# Smartcar.net
KiCad netlist of a schematic drawn in Altium Designer
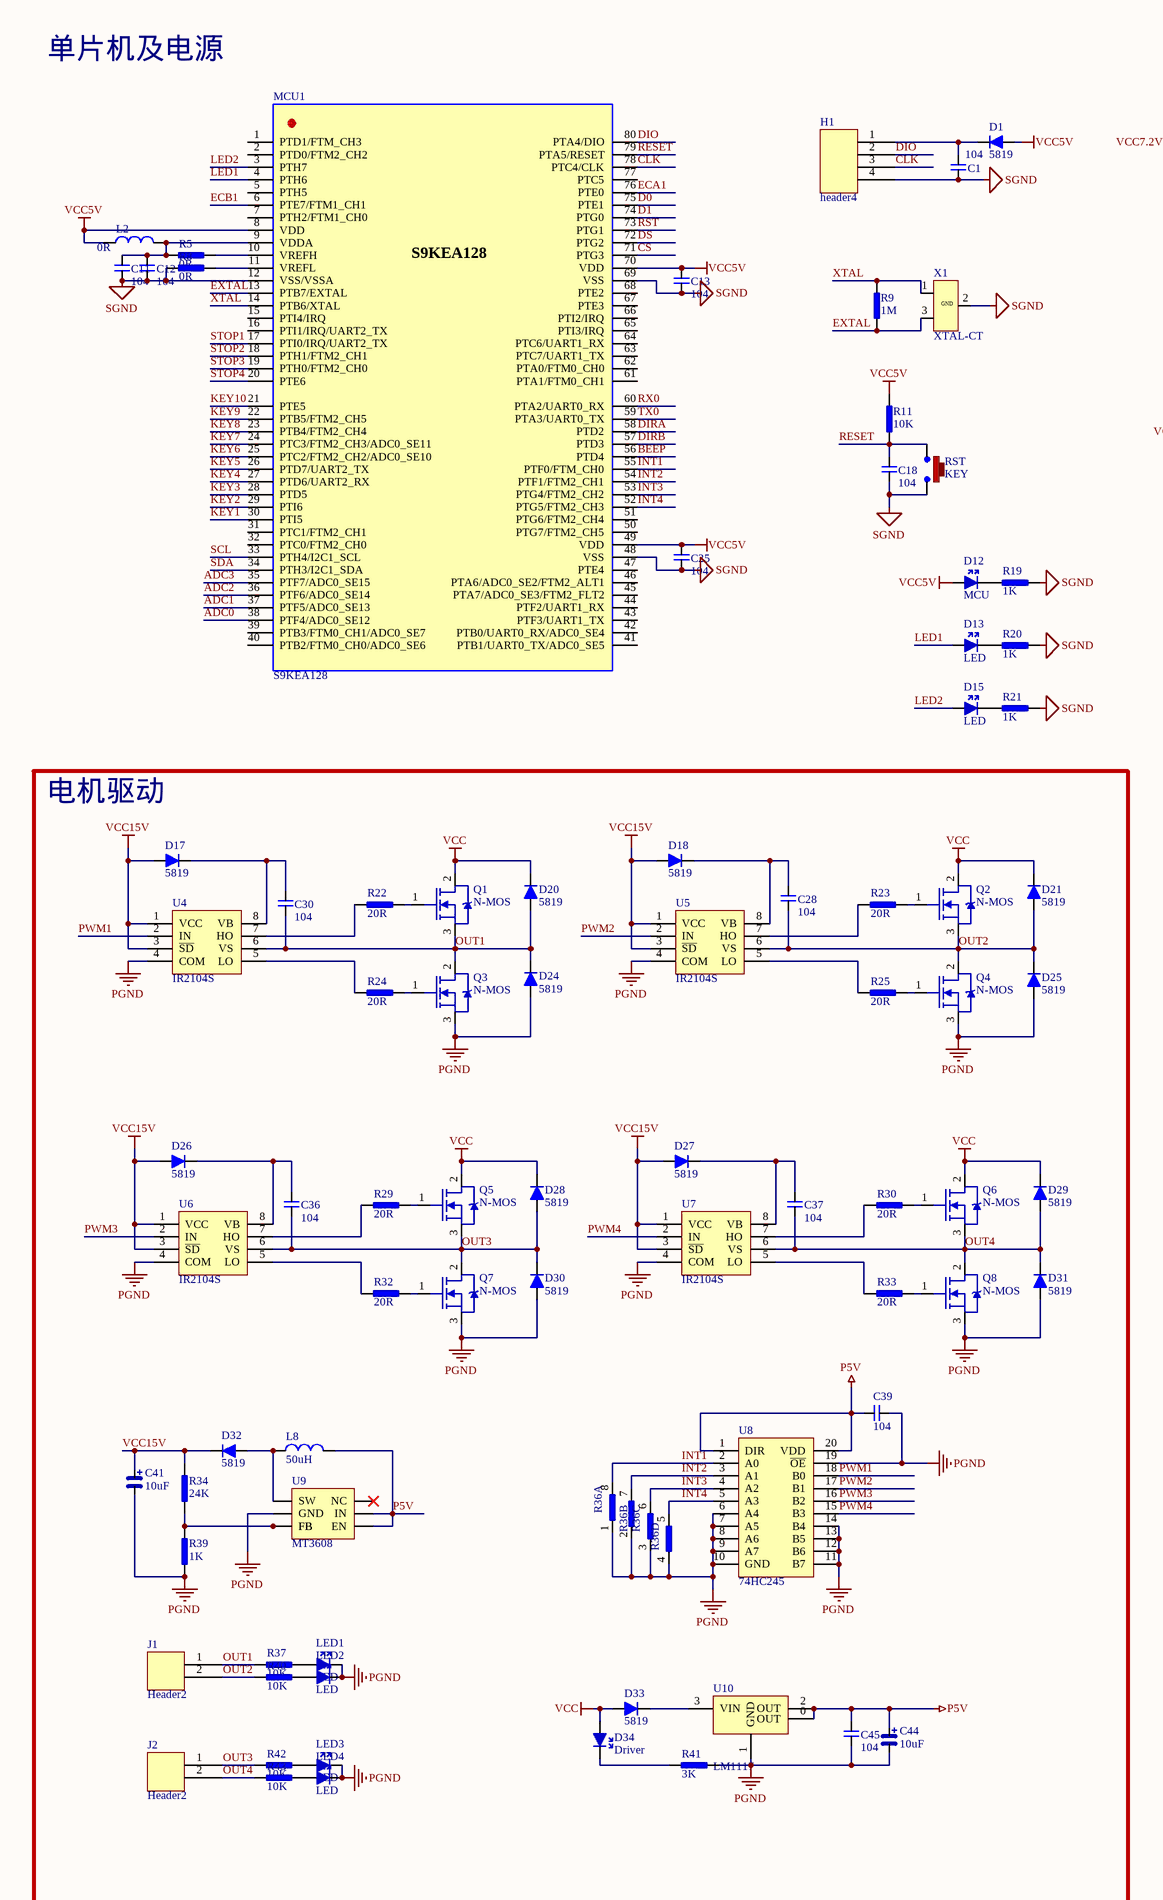
[diagram p0: Smartcar.SchDoc, left]
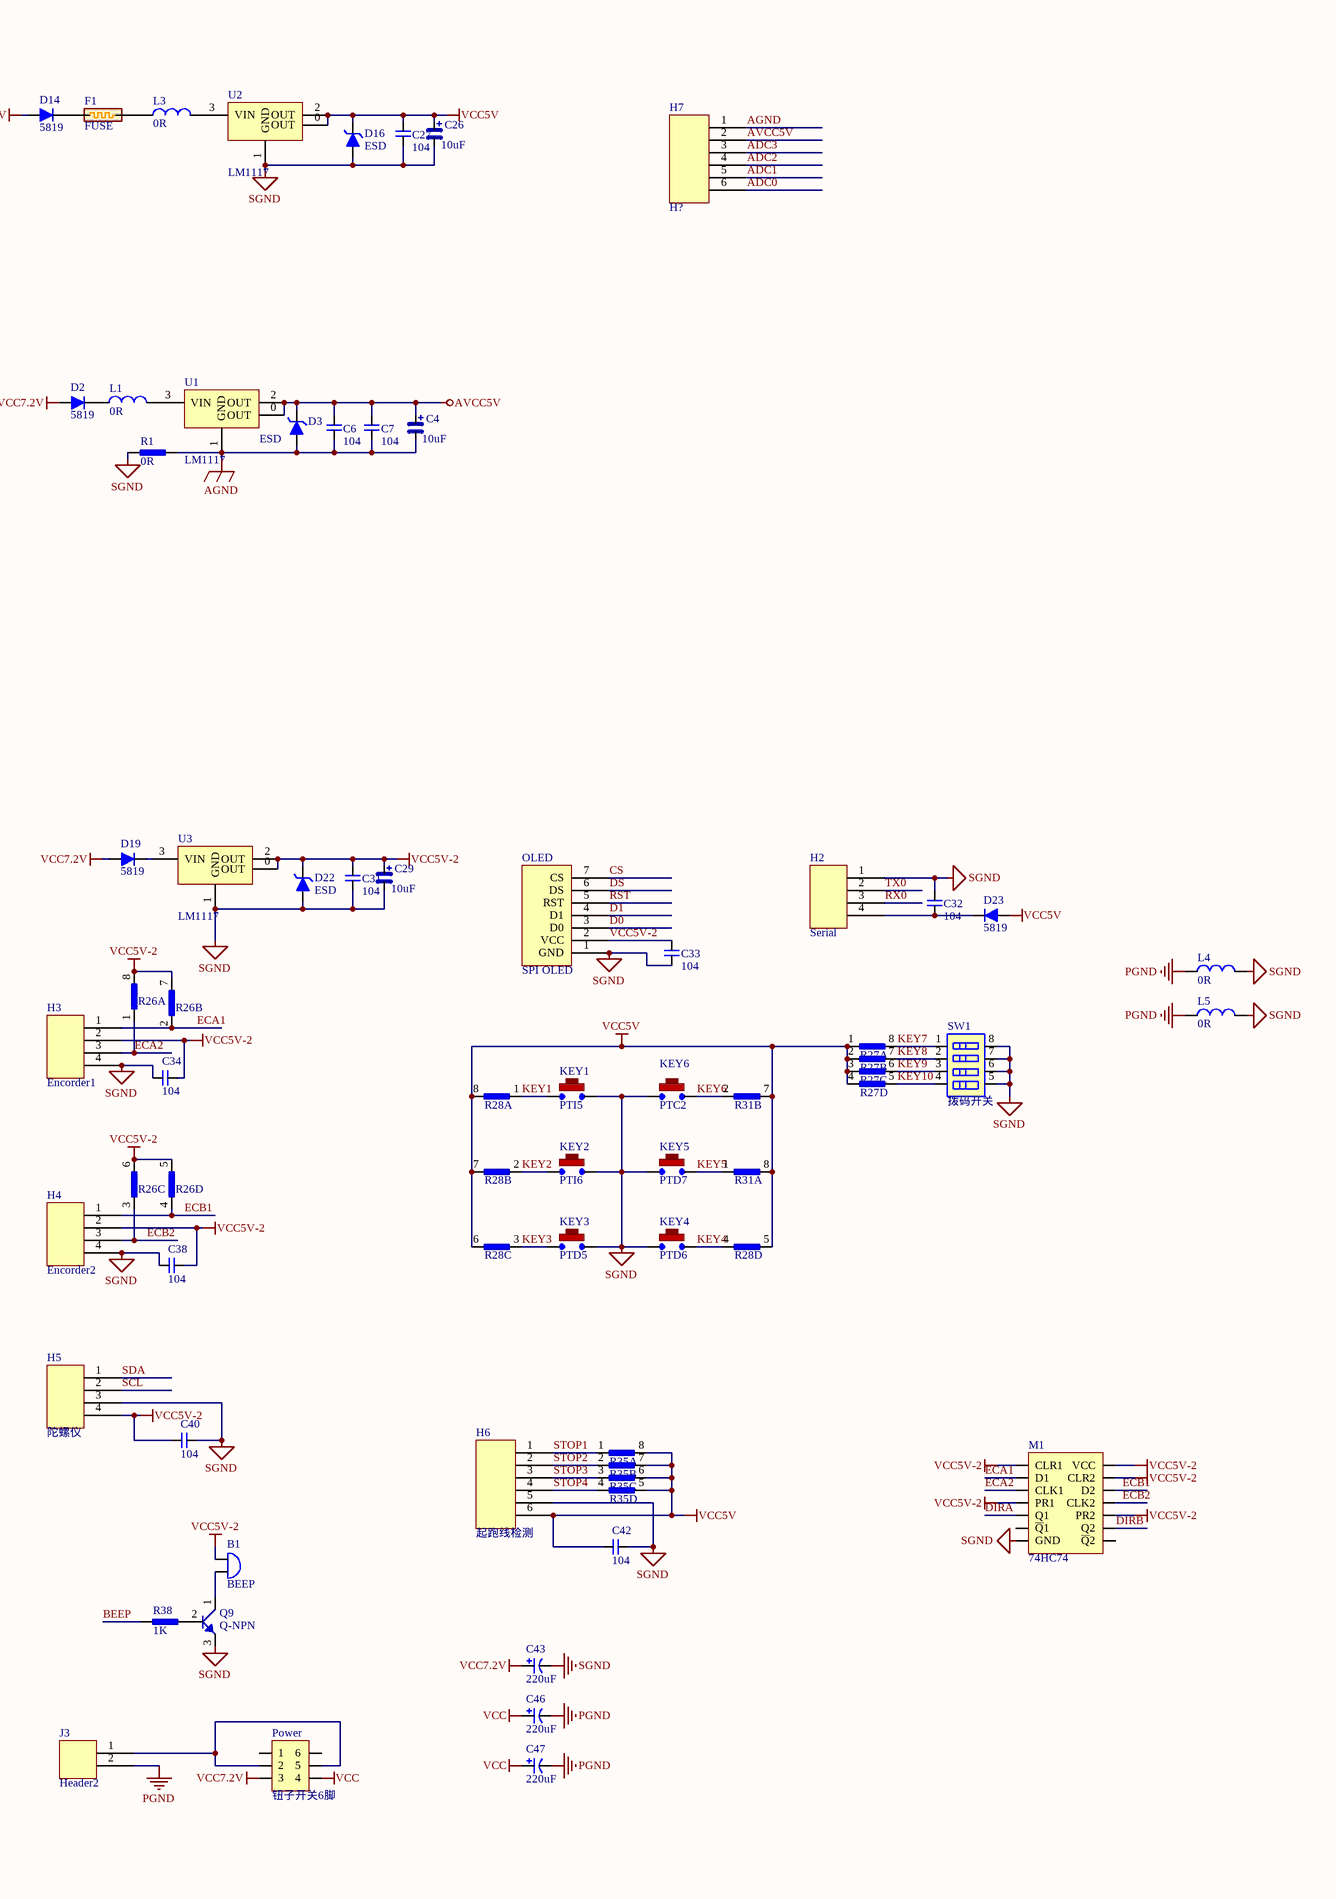
[diagram p1: Smartcar.SchDoc, right]

(export (version "E")
  (design (tool "Eeschema 10.0.6"))
  (components
    (comp (ref "B1") (value "BEEP") (footprint "BEEP") (libsource (lib "常用原理图库") (part "BEEP")))
    (comp (ref "C1") (value "104") (footprint "C0603") (libsource (lib "常用原理图库") (part "CAP")))
    (comp (ref "C4") (value "10uF") (footprint "TAN 3215") (libsource (lib "常用原理图库") (part "C-TAN")))
    (comp (ref "C6") (value "104") (footprint "C0603") (libsource (lib "常用原理图库") (part "CAP")))
    (comp (ref "C7") (value "104") (footprint "C0603") (libsource (lib "常用原理图库") (part "CAP")))
    (comp (ref "C11") (value "104") (footprint "C0603") (libsource (lib "常用原理图库") (part "CAP")))
    (comp (ref "C12") (value "104") (footprint "C0603") (libsource (lib "常用原理图库") (part "CAP")))
    (comp (ref "C13") (value "104") (footprint "C0603") (libsource (lib "常用原理图库") (part "CAP")))
    (comp (ref "C18") (value "104") (footprint "C0603") (libsource (lib "常用原理图库") (part "CAP")))
    (comp (ref "C25") (value "104") (footprint "C0603") (libsource (lib "常用原理图库") (part "CAP")))
    (comp (ref "C26") (value "10uF") (footprint "TAN 3215") (libsource (lib "常用原理图库") (part "C-TAN")))
    (comp (ref "C27") (value "104") (footprint "C0603") (libsource (lib "常用原理图库") (part "CAP")))
    (comp (ref "C28") (value "104") (footprint "C0603") (libsource (lib "常用原理图库") (part "CAP")))
    (comp (ref "C29") (value "10uF") (footprint "TAN 3215") (libsource (lib "常用原理图库") (part "C-TAN")))
    (comp (ref "C30") (value "104") (footprint "C0603") (libsource (lib "常用原理图库") (part "CAP")))
    (comp (ref "C31") (value "104") (footprint "C0603") (libsource (lib "常用原理图库") (part "CAP")))
    (comp (ref "C32") (value "104") (footprint "C0603") (libsource (lib "常用原理图库") (part "CAP")))
    (comp (ref "C33") (value "104") (footprint "C0603") (libsource (lib "常用原理图库") (part "CAP")))
    (comp (ref "C34") (value "104") (footprint "C0603") (libsource (lib "常用原理图库") (part "CAP")))
    (comp (ref "C36") (value "104") (footprint "C0603") (libsource (lib "常用原理图库") (part "CAP")))
    (comp (ref "C37") (value "104") (footprint "C0603") (libsource (lib "常用原理图库") (part "CAP")))
    (comp (ref "C38") (value "104") (footprint "C0603") (libsource (lib "常用原理图库") (part "CAP")))
    (comp (ref "C39") (value "104") (footprint "C0603") (libsource (lib "常用原理图库") (part "CAP")))
    (comp (ref "C40") (value "104") (footprint "C0603") (libsource (lib "常用原理图库") (part "CAP")))
    (comp (ref "C41") (value "10uF") (footprint "TAN 3215") (libsource (lib "常用原理图库") (part "C-TAN")))
    (comp (ref "C42") (value "104") (footprint "C0603") (libsource (lib "常用原理图库") (part "CAP")))
    (comp (ref "C43") (value "220uF") (footprint "CAP6.6X6.6") (libsource (lib "常用原理图库") (part "CAP-SMD")))
    (comp (ref "C44") (value "10uF") (footprint "TAN 3215") (libsource (lib "常用原理图库") (part "C-TAN")))
    (comp (ref "C45") (value "104") (footprint "C0603") (libsource (lib "常用原理图库") (part "CAP")))
    (comp (ref "C46") (value "220uF") (footprint "CAP6.6X6.6") (libsource (lib "常用原理图库") (part "CAP-SMD")))
    (comp (ref "C47") (value "220uF") (footprint "CAP6.6X6.6") (libsource (lib "常用原理图库") (part "CAP-SMD")))
    (comp (ref "D1") (value "5819") (footprint "SOD323") (libsource (lib "常用原理图库") (part "diode")))
    (comp (ref "D2") (value "5819") (footprint "SOD323") (libsource (lib "常用原理图库") (part "diode")))
    (comp (ref "D3") (value "ESD") (footprint "SOD323") (libsource (lib "常用原理图库") (part "D-ESD")))
    (comp (ref "D12") (value "MCU") (footprint "0603LED") (libsource (lib "常用原理图库") (part "LED")))
    (comp (ref "D13") (value "LED") (footprint "0603LED") (libsource (lib "常用原理图库") (part "LED")))
    (comp (ref "D14") (value "5819") (footprint "SOD123") (libsource (lib "常用原理图库") (part "diode")))
    (comp (ref "D15") (value "LED") (footprint "0603LED") (libsource (lib "常用原理图库") (part "LED")))
    (comp (ref "D16") (value "ESD") (footprint "SOD323") (libsource (lib "常用原理图库") (part "D-ESD")))
    (comp (ref "D17") (value "5819") (footprint "SOD123") (libsource (lib "常用原理图库") (part "Diode")))
    (comp (ref "D18") (value "5819") (footprint "SOD123") (libsource (lib "常用原理图库") (part "Diode")))
    (comp (ref "D19") (value "5819") (footprint "SOD323") (libsource (lib "常用原理图库") (part "diode")))
    (comp (ref "D20") (value "5819") (footprint "SOD323") (libsource (lib "常用原理图库") (part "Diode")))
    (comp (ref "D21") (value "5819") (footprint "SOD323") (libsource (lib "常用原理图库") (part "Diode")))
    (comp (ref "D22") (value "ESD") (footprint "SOD323") (libsource (lib "常用原理图库") (part "D-ESD")))
    (comp (ref "D23") (value "5819") (footprint "SOD323") (libsource (lib "常用原理图库") (part "Diode")))
    (comp (ref "D24") (value "5819") (footprint "SOD323") (libsource (lib "常用原理图库") (part "Diode")))
    (comp (ref "D25") (value "5819") (footprint "SOD323") (libsource (lib "常用原理图库") (part "Diode")))
    (comp (ref "D26") (value "5819") (footprint "SOD123") (libsource (lib "常用原理图库") (part "Diode")))
    (comp (ref "D27") (value "5819") (footprint "SOD123") (libsource (lib "常用原理图库") (part "Diode")))
    (comp (ref "D28") (value "5819") (footprint "SOD323") (libsource (lib "常用原理图库") (part "Diode")))
    (comp (ref "D29") (value "5819") (footprint "SOD323") (libsource (lib "常用原理图库") (part "Diode")))
    (comp (ref "D30") (value "5819") (footprint "SOD323") (libsource (lib "常用原理图库") (part "Diode")))
    (comp (ref "D31") (value "5819") (footprint "SOD323") (libsource (lib "常用原理图库") (part "Diode")))
    (comp (ref "D32") (value "5819") (footprint "SOD123") (libsource (lib "常用原理图库") (part "Diode")))
    (comp (ref "D33") (value "5819") (footprint "SOD123") (libsource (lib "常用原理图库") (part "diode")))
    (comp (ref "D34") (value "Driver") (footprint "0603LED") (libsource (lib "常用原理图库") (part "LED")))
    (comp (ref "F1") (value "FUSE") (footprint "R 0805") (libsource (lib "常用原理图库") (part "FUSE")))
    (comp (ref "H1") (value "header4") (footprint "HDR1X4") (libsource (lib "常用原理图库") (part "header4")))
    (comp (ref "H2") (value "Serial") (footprint "HDR1X4") (libsource (lib "常用原理图库") (part "header4")))
    (comp (ref "H3")
      (value "Encorder1")
      (footprint "1.25mm卧贴-4P")
      (libsource (lib "常用原理图库") (part "header4"))
    )
    (comp (ref "H4")
      (value "Encorder2")
      (footprint "1.25mm卧贴-4P")
      (libsource (lib "常用原理图库") (part "header4"))
    )
    (comp (ref "H5") (value "陀螺仪") (footprint "1.25mm卧贴-4P") (libsource (lib "常用原理图库") (part "header4")))
    (comp (ref "H6") (value "起跑线检测") (footprint "1.25mm卧贴-6P") (libsource (lib "常用原理图库") (part "header6")))
    (comp (ref "H7") (value "H?") (footprint "1.25mm卧贴-6P") (libsource (lib "常用原理图库") (part "header6")))
    (comp (ref "J1") (value "Header2") (footprint "motor") (libsource (lib "常用原理图库") (part "Header2")))
    (comp (ref "J2") (value "Header2") (footprint "MOTOR-R") (libsource (lib "常用原理图库") (part "Header2")))
    (comp (ref "J3") (value "Header2") (footprint "POWER-IN") (libsource (lib "常用原理图库") (part "Header2")))
    (comp (ref "KEY1") (value "PTI5") (footprint "轻触开关贴片") (libsource (lib "常用原理图库") (part "KEY")))
    (comp (ref "KEY2") (value "PTI6") (footprint "轻触开关贴片") (libsource (lib "常用原理图库") (part "KEY")))
    (comp (ref "KEY3") (value "PTD5") (footprint "轻触开关贴片") (libsource (lib "常用原理图库") (part "KEY")))
    (comp (ref "KEY4") (value "PTD6") (footprint "轻触开关贴片") (libsource (lib "常用原理图库") (part "KEY")))
    (comp (ref "KEY5") (value "PTD7") (footprint "轻触开关贴片") (libsource (lib "常用原理图库") (part "KEY")))
    (comp (ref "KEY6") (value "PTC2") (footprint "轻触开关贴片") (libsource (lib "常用原理图库") (part "KEY")))
    (comp (ref "L1") (value "0R") (footprint "L0603") (libsource (lib "常用原理图库") (part "Inductance")))
    (comp (ref "L2") (value "0R") (footprint "L0603") (libsource (lib "常用原理图库") (part "Inductance")))
    (comp (ref "L3") (value "0R") (footprint "L0603") (libsource (lib "常用原理图库") (part "Inductance")))
    (comp (ref "L4") (value "0R") (footprint "L0603") (libsource (lib "常用原理图库") (part "Inductance")))
    (comp (ref "L5") (value "0R") (footprint "L0603") (libsource (lib "常用原理图库") (part "Inductance")))
    (comp (ref "L8") (value "50uH") (footprint "L-06030") (libsource (lib "常用原理图库") (part "Inductance")))
    (comp (ref "LED1") (value "LED") (footprint "0603LED") (libsource (lib "常用原理图库") (part "LED")))
    (comp (ref "LED2") (value "LED") (footprint "0603LED") (libsource (lib "常用原理图库") (part "LED")))
    (comp (ref "LED3") (value "LED") (footprint "0603LED") (libsource (lib "常用原理图库") (part "LED")))
    (comp (ref "LED4") (value "LED") (footprint "0603LED") (libsource (lib "常用原理图库") (part "LED")))
    (comp (ref "M1") (value "74HC74") (footprint "ssoic14") (libsource (lib "常用原理图库") (part "74HC74")))
    (comp (ref "MCU1") (value "S9KEA128") (footprint "LQFP80") (libsource (lib "Smartcar") (part "S9KEA128")))
    (comp (ref "OLED")
      (value "SPI OLED")
      (footprint "OLED12864")
      (libsource (lib "常用原理图库") (part "SPI OLED"))
    )
    (comp (ref "Power") (value "钮子开关6脚") (footprint "钮子开关6脚") (libsource (lib "常用原理图库") (part "钮子开关6脚")))
    (comp (ref "Q1") (value "N-MOS") (footprint "常用封装:TO-252") (libsource (lib "常用原理图库") (part "N-MOS")))
    (comp (ref "Q2") (value "N-MOS") (footprint "常用封装:TO-252") (libsource (lib "常用原理图库") (part "N-MOS")))
    (comp (ref "Q3") (value "N-MOS") (footprint "常用封装:TO-252") (libsource (lib "常用原理图库") (part "N-MOS")))
    (comp (ref "Q4") (value "N-MOS") (footprint "常用封装:TO-252") (libsource (lib "常用原理图库") (part "N-MOS")))
    (comp (ref "Q5") (value "N-MOS") (footprint "常用封装:TO-252") (libsource (lib "常用原理图库") (part "N-MOS")))
    (comp (ref "Q6") (value "N-MOS") (footprint "常用封装:TO-252") (libsource (lib "常用原理图库") (part "N-MOS")))
    (comp (ref "Q7") (value "N-MOS") (footprint "常用封装:TO-252") (libsource (lib "常用原理图库") (part "N-MOS")))
    (comp (ref "Q8") (value "N-MOS") (footprint "常用封装:TO-252") (libsource (lib "常用原理图库") (part "N-MOS")))
    (comp (ref "Q9") (value "Q-NPN") (footprint "SOT-23") (libsource (lib "常用原理图库") (part "Q-NPN")))
    (comp (ref "R1") (value "0R") (footprint "R0603") (libsource (lib "常用原理图库") (part "RES")))
    (comp (ref "R5") (value "0R") (footprint "R0603") (libsource (lib "常用原理图库") (part "RES")))
    (comp (ref "R8") (value "0R") (footprint "R0603") (libsource (lib "常用原理图库") (part "RES")))
    (comp (ref "R9") (value "1M") (footprint "R0603") (libsource (lib "") (part "RES_1")))
    (comp (ref "R11") (value "10K") (footprint "R0603") (libsource (lib "") (part "RES_2")))
    (comp (ref "R19") (value "1K") (footprint "R0603") (libsource (lib "常用原理图库") (part "RES")))
    (comp (ref "R20") (value "1K") (footprint "R0603") (libsource (lib "常用原理图库") (part "RES")))
    (comp (ref "R21") (value "1K") (footprint "R0603") (libsource (lib "常用原理图库") (part "RES")))
    (comp (ref "R22") (value "20R") (footprint "R0603") (libsource (lib "常用原理图库") (part "RES")))
    (comp (ref "R23") (value "20R") (footprint "R0603") (libsource (lib "常用原理图库") (part "RES")))
    (comp (ref "R24") (value "20R") (footprint "R0603") (libsource (lib "常用原理图库") (part "RES")))
    (comp (ref "R25") (value "20R") (footprint "R0603") (libsource (lib "常用原理图库") (part "RES")))
    (comp (ref "R26")
      (value "Res Pack-4R")
      (footprint "8P4R-0603")
      (description "排阻")
      (fields (field (name "PUBLISHER") "Altium Limited"))
      (libsource (lib "") (part "Res Pack-4R_1"))
    )
    (comp (ref "R27")
      (value "Res Pack-4R")
      (footprint "8P4R-0603")
      (description "排阻")
      (fields (field (name "PUBLISHER") "Altium Limited"))
      (libsource (lib "常用原理图库") (part "Res Pack-4R"))
    )
    (comp (ref "R28")
      (value "Res Pack-4R")
      (footprint "8P4R-0603")
      (description "排阻")
      (fields (field (name "PUBLISHER") "Altium Limited"))
      (libsource (lib "常用原理图库") (part "Res Pack-4R"))
    )
    (comp (ref "R29") (value "20R") (footprint "R0603") (libsource (lib "常用原理图库") (part "RES")))
    (comp (ref "R30") (value "20R") (footprint "R0603") (libsource (lib "常用原理图库") (part "RES")))
    (comp (ref "R31")
      (value "Res Pack-4R")
      (footprint "8P4R-0603")
      (description "排阻")
      (fields (field (name "PUBLISHER") "Altium Limited"))
      (libsource (lib "常用原理图库") (part "Res Pack-4R"))
    )
    (comp (ref "R32") (value "20R") (footprint "R0603") (libsource (lib "常用原理图库") (part "RES")))
    (comp (ref "R33") (value "20R") (footprint "R0603") (libsource (lib "常用原理图库") (part "RES")))
    (comp (ref "R34") (value "24K") (footprint "R0603") (libsource (lib "") (part "RES_1")))
    (comp (ref "R35")
      (value "10K")
      (footprint "8P4R-0603")
      (description "排阻")
      (fields (field (name "PUBLISHER") "Altium Limited"))
      (libsource (lib "常用原理图库") (part "Res Pack-4R"))
    )
    (comp (ref "R36")
      (value "Res Pack-4R")
      (footprint "8P4R-0603")
      (description "排阻")
      (fields (field (name "PUBLISHER") "Altium Limited"))
      (libsource (lib "") (part "Res Pack-4R_1"))
    )
    (comp (ref "R37") (value "10K") (footprint "R0603") (libsource (lib "常用原理图库") (part "RES")))
    (comp (ref "R38") (value "1K") (footprint "R0603") (libsource (lib "常用原理图库") (part "RES")))
    (comp (ref "R39") (value "1K") (footprint "R0603") (libsource (lib "") (part "RES_1")))
    (comp (ref "R40") (value "10K") (footprint "R0603") (libsource (lib "常用原理图库") (part "RES")))
    (comp (ref "R41") (value "3K") (footprint "R0603") (libsource (lib "常用原理图库") (part "RES")))
    (comp (ref "R42") (value "10K") (footprint "R0603") (libsource (lib "常用原理图库") (part "RES")))
    (comp (ref "R43") (value "10K") (footprint "R0603") (libsource (lib "常用原理图库") (part "RES")))
    (comp (ref "RST") (value "KEY") (footprint "轻触开关贴片") (libsource (lib "") (part "KEY_1")))
    (comp (ref "SW1")
      (value "拨码开关")
      (footprint "SW-DIP-4 - duplicate")
      (libsource (lib "Smartcar") (part "拨码开关"))
    )
    (comp (ref "U1") (value "LM1117") (footprint "SOT223") (libsource (lib "") (part "1117_1")))
    (comp (ref "U2") (value "LM1117") (footprint "SOT223") (libsource (lib "常用原理图库") (part "1117")))
    (comp (ref "U3") (value "LM1117") (footprint "SOT223") (libsource (lib "常用原理图库") (part "1117")))
    (comp (ref "U4")
      (value "IR2104S")
      (footprint "SOP-8")
      (description "半桥驱动器")
      (libsource (lib "MOS电机驱动") (part "IR2104S"))
    )
    (comp (ref "U5")
      (value "IR2104S")
      (footprint "SOP-8")
      (description "半桥驱动器")
      (libsource (lib "MOS电机驱动") (part "IR2104S"))
    )
    (comp (ref "U6")
      (value "IR2104S")
      (footprint "SOP-8")
      (description "半桥驱动器")
      (libsource (lib "MOS电机驱动") (part "IR2104S"))
    )
    (comp (ref "U7")
      (value "IR2104S")
      (footprint "SOP-8")
      (description "半桥驱动器")
      (libsource (lib "MOS电机驱动") (part "IR2104S"))
    )
    (comp (ref "U8") (value "74HC245") (footprint "TSSOP-20") (libsource (lib "常用原理图库") (part "74HC245")))
    (comp (ref "U9") (value "MT3608") (footprint "SOT23-6") (libsource (lib "常用原理图库") (part "MT3608")))
    (comp (ref "U10") (value "LM1117") (footprint "SOT223") (libsource (lib "常用原理图库") (part "1117")))
    (comp (ref "X1") (value "XTAL-CT") (footprint "CSTCE8M") (libsource (lib "常用原理图库") (part "XTAL-CT")))
  )
  (nets
    (net (code "1") (name "/ADC0") (class "Default")
      (node (ref "H7") (pin "6") (pintype "passive"))
      (node (ref "MCU1") (pin "38") (pinfunction "PTF4/ADC0_SE12_38") (pintype "passive"))
    )
    (net (code "2") (name "/ADC1") (class "Default")
      (node (ref "H7") (pin "5") (pintype "passive"))
      (node (ref "MCU1") (pin "37") (pinfunction "PTF5/ADC0_SE13_37") (pintype "passive"))
    )
    (net (code "3") (name "/ADC2") (class "Default")
      (node (ref "H7") (pin "4") (pintype "passive"))
      (node (ref "MCU1") (pin "36") (pinfunction "PTF6/ADC0_SE14_36") (pintype "passive"))
    )
    (net (code "4") (name "/ADC3") (class "Default")
      (node (ref "H7") (pin "3") (pintype "passive"))
      (node (ref "MCU1") (pin "35") (pinfunction "PTF7/ADC0_SE15_35") (pintype "passive"))
    )
    (net (code "5") (name "/BEEP") (class "Default")
      (node (ref "MCU1") (pin "56") (pinfunction "PTD4_56") (pintype "passive"))
      (node (ref "R38") (pin "1") (pintype "passive"))
    )
    (net (code "6") (name "/CLK") (class "Default")
      (node (ref "H1") (pin "3") (pintype "passive"))
      (node (ref "MCU1") (pin "78") (pinfunction "PTC4/CLK_78") (pintype "passive"))
    )
    (net (code "7") (name "/CS") (class "Default")
      (node (ref "MCU1") (pin "71") (pinfunction "PTG3_71") (pintype "passive"))
      (node (ref "OLED") (pin "7") (pinfunction "CS_7") (pintype "passive"))
    )
    (net (code "8") (name "/D0") (class "Default")
      (node (ref "MCU1") (pin "75") (pinfunction "PTE1_75") (pintype "passive"))
      (node (ref "OLED") (pin "3") (pinfunction "D0_3") (pintype "passive"))
    )
    (net (code "9") (name "/D1") (class "Default")
      (node (ref "MCU1") (pin "74") (pinfunction "PTG0_74") (pintype "passive"))
      (node (ref "OLED") (pin "4") (pinfunction "D1_4") (pintype "passive"))
    )
    (net (code "10") (name "/DIO") (class "Default")
      (node (ref "H1") (pin "2") (pintype "passive"))
      (node (ref "MCU1") (pin "80") (pinfunction "PTA4/DIO_80") (pintype "passive"))
    )
    (net (code "11") (name "/DIRA") (class "Default")
      (node (ref "M1") (pin "5") (pinfunction "Q1_5") (pintype "passive"))
      (node (ref "MCU1") (pin "58") (pinfunction "PTD2_58") (pintype "passive"))
    )
    (net (code "12") (name "/DIRB") (class "Default")
      (node (ref "M1") (pin "9") (pinfunction "Q2_9") (pintype "passive"))
      (node (ref "MCU1") (pin "57") (pinfunction "PTD3_57") (pintype "passive"))
    )
    (net (code "13") (name "/DS") (class "Default")
      (node (ref "MCU1") (pin "72") (pinfunction "PTG2_72") (pintype "passive"))
      (node (ref "OLED") (pin "6") (pinfunction "DS_6") (pintype "passive"))
    )
    (net (code "14") (name "/ECA1") (class "Default")
      (node (ref "H3") (pin "1") (pintype "passive"))
      (node (ref "M1") (pin "2") (pinfunction "D1_2") (pintype "passive"))
      (node (ref "MCU1") (pin "76") (pinfunction "PTE0_76") (pintype "passive"))
      (node (ref "R26") (pin "2") (pinfunction "2_2") (pintype "passive"))
    )
    (net (code "15") (name "/ECA2") (class "Default")
      (node (ref "H3") (pin "3") (pintype "passive"))
      (node (ref "M1") (pin "3") (pinfunction "CLK1_3") (pintype "passive"))
      (node (ref "R26") (pin "1") (pinfunction "1_1") (pintype "passive"))
    )
    (net (code "16") (name "/ECB1") (class "Default")
      (node (ref "H4") (pin "1") (pintype "passive"))
      (node (ref "M1") (pin "12") (pinfunction "D2_12") (pintype "passive"))
      (node (ref "MCU1") (pin "6") (pinfunction "PTE7/FTM1_CH1_6") (pintype "passive"))
      (node (ref "R26") (pin "4") (pinfunction "4_4") (pintype "passive"))
    )
    (net (code "17") (name "/ECB2") (class "Default")
      (node (ref "H4") (pin "3") (pintype "passive"))
      (node (ref "M1") (pin "11") (pinfunction "CLK2_11") (pintype "passive"))
      (node (ref "R26") (pin "3") (pinfunction "3_3") (pintype "passive"))
    )
    (net (code "18") (name "/EXTAL") (class "Default")
      (node (ref "MCU1") (pin "13") (pinfunction "PTB7/EXTAL_13") (pintype "passive"))
      (node (ref "R9") (pin "1") (pintype "passive"))
      (node (ref "X1") (pin "3") (pintype "passive"))
    )
    (net (code "19") (name "/INT1") (class "Default")
      (node (ref "MCU1") (pin "55") (pinfunction "PTF0/FTM_CH0_55") (pintype "passive"))
      (node (ref "R36") (pin "8") (pinfunction "8_8") (pintype "passive"))
      (node (ref "U8") (pin "2") (pinfunction "A0_2") (pintype "passive"))
    )
    (net (code "20") (name "/INT2") (class "Default")
      (node (ref "MCU1") (pin "54") (pinfunction "PTF1/FTM2_CH1_54") (pintype "passive"))
      (node (ref "R36") (pin "7") (pinfunction "7_7") (pintype "passive"))
      (node (ref "U8") (pin "3") (pinfunction "A1_3") (pintype "passive"))
    )
    (net (code "21") (name "/INT3") (class "Default")
      (node (ref "MCU1") (pin "53") (pinfunction "PTG4/FTM2_CH2_53") (pintype "passive"))
      (node (ref "R36") (pin "6") (pinfunction "6_6") (pintype "passive"))
      (node (ref "U8") (pin "4") (pinfunction "A2_4") (pintype "passive"))
    )
    (net (code "22") (name "/INT4") (class "Default")
      (node (ref "MCU1") (pin "52") (pinfunction "PTG5/FTM2_CH3_52") (pintype "passive"))
      (node (ref "R36") (pin "5") (pinfunction "5_5") (pintype "passive"))
      (node (ref "U8") (pin "5") (pinfunction "A3_5") (pintype "passive"))
    )
    (net (code "23") (name "/KEY1") (class "Default")
      (node (ref "KEY1") (pin "1") (pintype "passive"))
      (node (ref "MCU1") (pin "30") (pinfunction "PTI5_30") (pintype "passive"))
      (node (ref "R28") (pin "1") (pinfunction "1_1") (pintype "passive"))
    )
    (net (code "24") (name "/KEY2") (class "Default")
      (node (ref "KEY2") (pin "1") (pintype "passive"))
      (node (ref "MCU1") (pin "29") (pinfunction "PTI6_29") (pintype "passive"))
      (node (ref "R28") (pin "2") (pinfunction "2_2") (pintype "passive"))
    )
    (net (code "25") (name "/KEY3") (class "Default")
      (node (ref "KEY3") (pin "1") (pintype "passive"))
      (node (ref "MCU1") (pin "28") (pinfunction "PTD5_28") (pintype "passive"))
      (node (ref "R28") (pin "3") (pinfunction "3_3") (pintype "passive"))
    )
    (net (code "26") (name "/KEY4") (class "Default")
      (node (ref "KEY4") (pin "2") (pintype "passive"))
      (node (ref "MCU1") (pin "27") (pinfunction "PTD6/UART2_RX_27") (pintype "passive"))
      (node (ref "R28") (pin "4") (pinfunction "4_4") (pintype "passive"))
    )
    (net (code "27") (name "/KEY5") (class "Default")
      (node (ref "KEY5") (pin "2") (pintype "passive"))
      (node (ref "MCU1") (pin "26") (pinfunction "PTD7/UART2_TX_26") (pintype "passive"))
      (node (ref "R31") (pin "1") (pinfunction "1_1") (pintype "passive"))
    )
    (net (code "28") (name "/KEY6") (class "Default")
      (node (ref "KEY6") (pin "2") (pintype "passive"))
      (node (ref "MCU1") (pin "25") (pinfunction "PTC2/FTM2_CH2/ADC0_SE10_25") (pintype "passive"))
      (node (ref "R31") (pin "2") (pinfunction "2_2") (pintype "passive"))
    )
    (net (code "29") (name "/KEY7") (class "Default")
      (node (ref "MCU1") (pin "24") (pinfunction "PTC3/FTM2_CH3/ADC0_SE11_24") (pintype "passive"))
      (node (ref "R27") (pin "8") (pinfunction "8_8") (pintype "passive"))
      (node (ref "SW1") (pin "1") (pintype "passive"))
    )
    (net (code "30") (name "/KEY8") (class "Default")
      (node (ref "MCU1") (pin "23") (pinfunction "PTB4/FTM2_CH4_23") (pintype "passive"))
      (node (ref "R27") (pin "7") (pinfunction "7_7") (pintype "passive"))
      (node (ref "SW1") (pin "2") (pintype "passive"))
    )
    (net (code "31") (name "/KEY9") (class "Default")
      (node (ref "MCU1") (pin "22") (pinfunction "PTB5/FTM2_CH5_22") (pintype "passive"))
      (node (ref "R27") (pin "6") (pinfunction "6_6") (pintype "passive"))
      (node (ref "SW1") (pin "3") (pintype "passive"))
    )
    (net (code "32") (name "/KEY10") (class "Default")
      (node (ref "MCU1") (pin "21") (pinfunction "PTE5_21") (pintype "passive"))
      (node (ref "R27") (pin "5") (pinfunction "5_5") (pintype "passive"))
      (node (ref "SW1") (pin "4") (pintype "passive"))
    )
    (net (code "33") (name "/LED1") (class "Default")
      (node (ref "D13") (pin "1") (pintype "passive"))
      (node (ref "MCU1") (pin "4") (pinfunction "PTH6_4") (pintype "passive"))
    )
    (net (code "34") (name "/LED2") (class "Default")
      (node (ref "D15") (pin "1") (pintype "passive"))
      (node (ref "MCU1") (pin "3") (pinfunction "PTH7_3") (pintype "passive"))
    )
    (net (code "35") (name "/OUT1") (class "Default")
      (node (ref "C30") (pin "2") (pintype "passive"))
      (node (ref "D20") (pin "1") (pintype "passive"))
      (node (ref "D24") (pin "2") (pintype "passive"))
      (node (ref "J1") (pin "1") (pintype "passive"))
      (node (ref "Q1") (pin "3") (pintype "passive"))
      (node (ref "Q3") (pin "2") (pintype "passive"))
      (node (ref "R37") (pin "1") (pintype "passive"))
      (node (ref "U4") (pin "6") (pinfunction "VS_6") (pintype "passive"))
    )
    (net (code "36") (name "/OUT2") (class "Default")
      (node (ref "C28") (pin "2") (pintype "passive"))
      (node (ref "D21") (pin "1") (pintype "passive"))
      (node (ref "D25") (pin "2") (pintype "passive"))
      (node (ref "J1") (pin "2") (pintype "passive"))
      (node (ref "Q2") (pin "3") (pintype "passive"))
      (node (ref "Q4") (pin "2") (pintype "passive"))
      (node (ref "R40") (pin "1") (pintype "passive"))
      (node (ref "U5") (pin "6") (pinfunction "VS_6") (pintype "passive"))
    )
    (net (code "37") (name "/OUT3") (class "Default")
      (node (ref "C36") (pin "2") (pintype "passive"))
      (node (ref "D28") (pin "1") (pintype "passive"))
      (node (ref "D30") (pin "2") (pintype "passive"))
      (node (ref "J2") (pin "1") (pintype "passive"))
      (node (ref "Q5") (pin "3") (pintype "passive"))
      (node (ref "Q7") (pin "2") (pintype "passive"))
      (node (ref "R42") (pin "1") (pintype "passive"))
      (node (ref "U6") (pin "6") (pinfunction "VS_6") (pintype "passive"))
    )
    (net (code "38") (name "/OUT4") (class "Default")
      (node (ref "C37") (pin "2") (pintype "passive"))
      (node (ref "D29") (pin "1") (pintype "passive"))
      (node (ref "D31") (pin "2") (pintype "passive"))
      (node (ref "J2") (pin "2") (pintype "passive"))
      (node (ref "Q6") (pin "3") (pintype "passive"))
      (node (ref "Q8") (pin "2") (pintype "passive"))
      (node (ref "R43") (pin "1") (pintype "passive"))
      (node (ref "U7") (pin "6") (pinfunction "VS_6") (pintype "passive"))
    )
    (net (code "39") (name "/PWM1") (class "Default")
      (node (ref "U4") (pin "2") (pinfunction "IN_2") (pintype "passive"))
      (node (ref "U8") (pin "18") (pinfunction "B0_18") (pintype "passive"))
    )
    (net (code "40") (name "/PWM2") (class "Default")
      (node (ref "U5") (pin "2") (pinfunction "IN_2") (pintype "passive"))
      (node (ref "U8") (pin "17") (pinfunction "B1_17") (pintype "passive"))
    )
    (net (code "41") (name "/PWM3") (class "Default")
      (node (ref "U6") (pin "2") (pinfunction "IN_2") (pintype "passive"))
      (node (ref "U8") (pin "16") (pinfunction "B2_16") (pintype "passive"))
    )
    (net (code "42") (name "/PWM4") (class "Default")
      (node (ref "U7") (pin "2") (pinfunction "IN_2") (pintype "passive"))
      (node (ref "U8") (pin "15") (pinfunction "B3_15") (pintype "passive"))
    )
    (net (code "43") (name "/RESET") (class "Default")
      (node (ref "C18") (pin "1") (pintype "passive"))
      (node (ref "MCU1") (pin "79") (pinfunction "PTA5/RESET_79") (pintype "passive"))
      (node (ref "R11") (pin "2") (pintype "passive"))
      (node (ref "RST") (pin "1") (pintype "passive"))
    )
    (net (code "44") (name "/RST") (class "Default")
      (node (ref "MCU1") (pin "73") (pinfunction "PTG1_73") (pintype "passive"))
      (node (ref "OLED") (pin "5") (pinfunction "RST_5") (pintype "passive"))
    )
    (net (code "45") (name "/RX0") (class "Default")
      (node (ref "H2") (pin "3") (pintype "passive"))
      (node (ref "MCU1") (pin "60") (pinfunction "PTA2/UART0_RX_60") (pintype "passive"))
    )
    (net (code "46") (name "/SCL") (class "Default")
      (node (ref "H5") (pin "2") (pintype "passive"))
      (node (ref "MCU1") (pin "33") (pinfunction "PTH4/I2C1_SCL_33") (pintype "passive"))
    )
    (net (code "47") (name "/SDA") (class "Default")
      (node (ref "H5") (pin "1") (pintype "passive"))
      (node (ref "MCU1") (pin "34") (pinfunction "PTH3/I2C1_SDA_34") (pintype "passive"))
    )
    (net (code "48") (name "/STOP1") (class "Default")
      (node (ref "H6") (pin "1") (pintype "passive"))
      (node (ref "MCU1") (pin "17") (pinfunction "PTI0/IRQ/UART2_TX_17") (pintype "passive"))
      (node (ref "R35") (pin "1") (pinfunction "1_1") (pintype "passive"))
    )
    (net (code "49") (name "/STOP2") (class "Default")
      (node (ref "H6") (pin "2") (pintype "passive"))
      (node (ref "MCU1") (pin "18") (pinfunction "PTH1/FTM2_CH1_18") (pintype "passive"))
      (node (ref "R35") (pin "2") (pinfunction "2_2") (pintype "passive"))
    )
    (net (code "50") (name "/STOP3") (class "Default")
      (node (ref "H6") (pin "3") (pintype "passive"))
      (node (ref "MCU1") (pin "19") (pinfunction "PTH0/FTM2_CH0_19") (pintype "passive"))
      (node (ref "R35") (pin "3") (pinfunction "3_3") (pintype "passive"))
    )
    (net (code "51") (name "/STOP4") (class "Default")
      (node (ref "H6") (pin "4") (pintype "passive"))
      (node (ref "MCU1") (pin "20") (pinfunction "PTE6_20") (pintype "passive"))
      (node (ref "R35") (pin "4") (pinfunction "4_4") (pintype "passive"))
    )
    (net (code "52") (name "/TX0") (class "Default")
      (node (ref "H2") (pin "2") (pintype "passive"))
      (node (ref "MCU1") (pin "59") (pinfunction "PTA3/UART0_TX_59") (pintype "passive"))
    )
    (net (code "53") (name "/XTAL") (class "Default")
      (node (ref "MCU1") (pin "14") (pinfunction "PTB6/XTAL_14") (pintype "passive"))
      (node (ref "R9") (pin "2") (pintype "passive"))
      (node (ref "X1") (pin "1") (pintype "passive"))
    )
    (net (code "54") (name "AGND") (class "Default")
      (node (ref "C4") (pin "2") (pintype "passive"))
      (node (ref "C6") (pin "1") (pintype "passive"))
      (node (ref "C7") (pin "1") (pintype "passive"))
      (node (ref "D3") (pin "1") (pintype "passive"))
      (node (ref "H7") (pin "1") (pintype "passive"))
      (node (ref "R1") (pin "2") (pintype "passive"))
      (node (ref "U1") (pin "1") (pinfunction "GND_1") (pintype "passive"))
    )
    (net (code "55") (name "AVCC5V") (class "Default")
      (node (ref "C4") (pin "1") (pintype "passive"))
      (node (ref "C6") (pin "2") (pintype "passive"))
      (node (ref "C7") (pin "2") (pintype "passive"))
      (node (ref "D3") (pin "2") (pintype "passive"))
      (node (ref "H7") (pin "2") (pintype "passive"))
      (node (ref "U1") (pin "0") (pinfunction "OUT_0") (pintype "passive"))
      (node (ref "U1") (pin "2") (pinfunction "OUT_2") (pintype "passive"))
    )
    (net (code "56") (name "Net-(B1-Pad2)") (class "Default")
      (node (ref "B1") (pin "2") (pintype "passive"))
      (node (ref "Q9") (pin "1") (pinfunction "1_1") (pintype "passive"))
    )
    (net (code "57") (name "Net-(C1-Pad2)") (class "Default")
      (node (ref "C1") (pin "2") (pintype "passive"))
      (node (ref "D1") (pin "2") (pintype "passive"))
      (node (ref "H1") (pin "1") (pintype "passive"))
    )
    (net (code "58") (name "Net-(C32-Pad2)") (class "Default")
      (node (ref "C32") (pin "2") (pintype "passive"))
      (node (ref "D23") (pin "2") (pintype "passive"))
      (node (ref "H2") (pin "4") (pintype "passive"))
    )
    (net (code "59") (name "Net-(D2-Pad2)") (class "Default")
      (node (ref "D2") (pin "2") (pintype "passive"))
      (node (ref "L1") (pin "2") (pinfunction "2_2") (pintype "passive"))
    )
    (net (code "60") (name "Net-(D12-Pad2)") (class "Default")
      (node (ref "D12") (pin "2") (pintype "passive"))
      (node (ref "R19") (pin "1") (pintype "passive"))
    )
    (net (code "61") (name "Net-(D13-Pad2)") (class "Default")
      (node (ref "D13") (pin "2") (pintype "passive"))
      (node (ref "R20") (pin "1") (pintype "passive"))
    )
    (net (code "62") (name "Net-(D14-Pad2)") (class "Default")
      (node (ref "D14") (pin "2") (pintype "passive"))
      (node (ref "F1") (pin "1") (pintype "passive"))
    )
    (net (code "63") (name "Net-(D15-Pad2)") (class "Default")
      (node (ref "D15") (pin "2") (pintype "passive"))
      (node (ref "R21") (pin "1") (pintype "passive"))
    )
    (net (code "64") (name "Net-(D34-Pad2)") (class "Default")
      (node (ref "D34") (pin "2") (pintype "passive"))
      (node (ref "R41") (pin "1") (pintype "passive"))
    )
    (net (code "65") (name "Net-(F1-Pad2)") (class "Default")
      (node (ref "F1") (pin "2") (pintype "passive"))
      (node (ref "L3") (pin "2") (pinfunction "2_2") (pintype "passive"))
    )
    (net (code "66") (name "Net-(J3-Pad1)") (class "Default")
      (node (ref "J3") (pin "1") (pintype "passive"))
      (node (ref "Power") (pin "2") (pinfunction "2_2") (pintype "passive"))
      (node (ref "Power") (pin "5") (pinfunction "5_5") (pintype "passive"))
    )
    (net (code "67") (name "Net-(LED1-Pad1)") (class "Default")
      (node (ref "LED1") (pin "1") (pintype "passive"))
      (node (ref "R37") (pin "2") (pintype "passive"))
    )
    (net (code "68") (name "Net-(LED2-Pad1)") (class "Default")
      (node (ref "LED2") (pin "1") (pintype "passive"))
      (node (ref "R40") (pin "2") (pintype "passive"))
    )
    (net (code "69") (name "Net-(LED3-Pad1)") (class "Default")
      (node (ref "LED3") (pin "1") (pintype "passive"))
      (node (ref "R42") (pin "2") (pintype "passive"))
    )
    (net (code "70") (name "Net-(LED4-Pad1)") (class "Default")
      (node (ref "LED4") (pin "1") (pintype "passive"))
      (node (ref "R43") (pin "2") (pintype "passive"))
    )
    (net (code "71") (name "Net-(MCU1-VDDA)") (class "Default")
      (node (ref "C11") (pin "2") (pintype "passive"))
      (node (ref "C12") (pin "2") (pintype "passive"))
      (node (ref "L2") (pin "1") (pinfunction "1_1") (pintype "passive"))
      (node (ref "MCU1") (pin "9") (pinfunction "VDDA_9") (pintype "passive"))
      (node (ref "R5") (pin "1") (pintype "passive"))
    )
    (net (code "72") (name "Net-(MCU1-VREFH)") (class "Default")
      (node (ref "MCU1") (pin "10") (pinfunction "VREFH_10") (pintype "passive"))
      (node (ref "R5") (pin "2") (pintype "passive"))
    )
    (net (code "73") (name "Net-(MCU1-VREFL)") (class "Default")
      (node (ref "MCU1") (pin "11") (pinfunction "VREFL_11") (pintype "passive"))
      (node (ref "R8") (pin "2") (pintype "passive"))
    )
    (net (code "74") (name "Net-(Q1-Pad1)") (class "Default")
      (node (ref "Q1") (pin "1") (pintype "passive"))
      (node (ref "R22") (pin "2") (pintype "passive"))
    )
    (net (code "75") (name "Net-(Q2-Pad1)") (class "Default")
      (node (ref "Q2") (pin "1") (pintype "passive"))
      (node (ref "R23") (pin "2") (pintype "passive"))
    )
    (net (code "76") (name "Net-(Q3-Pad1)") (class "Default")
      (node (ref "Q3") (pin "1") (pintype "passive"))
      (node (ref "R24") (pin "2") (pintype "passive"))
    )
    (net (code "77") (name "Net-(Q4-Pad1)") (class "Default")
      (node (ref "Q4") (pin "1") (pintype "passive"))
      (node (ref "R25") (pin "2") (pintype "passive"))
    )
    (net (code "78") (name "Net-(Q5-Pad1)") (class "Default")
      (node (ref "Q5") (pin "1") (pintype "passive"))
      (node (ref "R29") (pin "2") (pintype "passive"))
    )
    (net (code "79") (name "Net-(Q6-Pad1)") (class "Default")
      (node (ref "Q6") (pin "1") (pintype "passive"))
      (node (ref "R30") (pin "2") (pintype "passive"))
    )
    (net (code "80") (name "Net-(Q7-Pad1)") (class "Default")
      (node (ref "Q7") (pin "1") (pintype "passive"))
      (node (ref "R32") (pin "2") (pintype "passive"))
    )
    (net (code "81") (name "Net-(Q8-Pad1)") (class "Default")
      (node (ref "Q8") (pin "1") (pintype "passive"))
      (node (ref "R33") (pin "2") (pintype "passive"))
    )
    (net (code "82") (name "Net-(Q9-Pad2)") (class "Default")
      (node (ref "Q9") (pin "2") (pinfunction "2_2") (pintype "passive"))
      (node (ref "R38") (pin "2") (pintype "passive"))
    )
    (net (code "83") (name "Net-(U1-VIN)") (class "Default")
      (node (ref "L1") (pin "1") (pinfunction "1_1") (pintype "passive"))
      (node (ref "U1") (pin "3") (pinfunction "VIN_3") (pintype "passive"))
    )
    (net (code "84") (name "Net-(U2-VIN)") (class "Default")
      (node (ref "L3") (pin "1") (pinfunction "1_1") (pintype "passive"))
      (node (ref "U2") (pin "3") (pinfunction "VIN_3") (pintype "passive"))
    )
    (net (code "85") (name "Net-(U3-VIN)") (class "Default")
      (node (ref "D19") (pin "2") (pintype "passive"))
      (node (ref "U3") (pin "3") (pinfunction "VIN_3") (pintype "passive"))
    )
    (net (code "86") (name "Net-(U4-HO)") (class "Default")
      (node (ref "R22") (pin "1") (pintype "passive"))
      (node (ref "U4") (pin "7") (pinfunction "HO_7") (pintype "passive"))
    )
    (net (code "87") (name "Net-(U4-LO)") (class "Default")
      (node (ref "R24") (pin "1") (pintype "passive"))
      (node (ref "U4") (pin "5") (pinfunction "LO_5") (pintype "passive"))
    )
    (net (code "88") (name "Net-(U4-VB)") (class "Default")
      (node (ref "C30") (pin "1") (pintype "passive"))
      (node (ref "D17") (pin "2") (pintype "passive"))
      (node (ref "U4") (pin "8") (pinfunction "VB_8") (pintype "passive"))
    )
    (net (code "89") (name "Net-(U5-HO)") (class "Default")
      (node (ref "R23") (pin "1") (pintype "passive"))
      (node (ref "U5") (pin "7") (pinfunction "HO_7") (pintype "passive"))
    )
    (net (code "90") (name "Net-(U5-LO)") (class "Default")
      (node (ref "R25") (pin "1") (pintype "passive"))
      (node (ref "U5") (pin "5") (pinfunction "LO_5") (pintype "passive"))
    )
    (net (code "91") (name "Net-(U5-VB)") (class "Default")
      (node (ref "C28") (pin "1") (pintype "passive"))
      (node (ref "D18") (pin "2") (pintype "passive"))
      (node (ref "U5") (pin "8") (pinfunction "VB_8") (pintype "passive"))
    )
    (net (code "92") (name "Net-(U6-HO)") (class "Default")
      (node (ref "R29") (pin "1") (pintype "passive"))
      (node (ref "U6") (pin "7") (pinfunction "HO_7") (pintype "passive"))
    )
    (net (code "93") (name "Net-(U6-LO)") (class "Default")
      (node (ref "R32") (pin "1") (pintype "passive"))
      (node (ref "U6") (pin "5") (pinfunction "LO_5") (pintype "passive"))
    )
    (net (code "94") (name "Net-(U6-VB)") (class "Default")
      (node (ref "C36") (pin "1") (pintype "passive"))
      (node (ref "D26") (pin "2") (pintype "passive"))
      (node (ref "U6") (pin "8") (pinfunction "VB_8") (pintype "passive"))
    )
    (net (code "95") (name "Net-(U7-HO)") (class "Default")
      (node (ref "R30") (pin "1") (pintype "passive"))
      (node (ref "U7") (pin "7") (pinfunction "HO_7") (pintype "passive"))
    )
    (net (code "96") (name "Net-(U7-LO)") (class "Default")
      (node (ref "R33") (pin "1") (pintype "passive"))
      (node (ref "U7") (pin "5") (pinfunction "LO_5") (pintype "passive"))
    )
    (net (code "97") (name "Net-(U7-VB)") (class "Default")
      (node (ref "C37") (pin "1") (pintype "passive"))
      (node (ref "D27") (pin "2") (pintype "passive"))
      (node (ref "U7") (pin "8") (pinfunction "VB_8") (pintype "passive"))
    )
    (net (code "98") (name "Net-(U9-FB)") (class "Default")
      (node (ref "R34") (pin "1") (pintype "passive"))
      (node (ref "R39") (pin "2") (pintype "passive"))
      (node (ref "U9") (pin "3") (pinfunction "FB_3") (pintype "passive"))
    )
    (net (code "99") (name "Net-(U9-SW)") (class "Default")
      (node (ref "D32") (pin "1") (pintype "passive"))
      (node (ref "L8") (pin "2") (pinfunction "2_2") (pintype "passive"))
      (node (ref "U9") (pin "1") (pinfunction "SW_1") (pintype "passive"))
    )
    (net (code "100") (name "Net-(U10-VIN)") (class "Default")
      (node (ref "D33") (pin "2") (pintype "passive"))
      (node (ref "U10") (pin "3") (pinfunction "VIN_3") (pintype "passive"))
    )
    (net (code "101") (name "P5V") (class "Default")
      (node (ref "C39") (pin "1") (pintype "passive"))
      (node (ref "C44") (pin "1") (pintype "passive"))
      (node (ref "C45") (pin "2") (pintype "passive"))
      (node (ref "L8") (pin "1") (pinfunction "1_1") (pintype "passive"))
      (node (ref "U10") (pin "0") (pinfunction "OUT_0") (pintype "passive"))
      (node (ref "U10") (pin "2") (pinfunction "OUT_2") (pintype "passive"))
      (node (ref "U8") (pin "1") (pinfunction "DIR_1") (pintype "passive"))
      (node (ref "U8") (pin "20") (pinfunction "VDD_20") (pintype "passive"))
      (node (ref "U9") (pin "4") (pinfunction "EN_4") (pintype "passive"))
      (node (ref "U9") (pin "5") (pinfunction "IN_5") (pintype "passive"))
    )
    (net (code "102") (name "PGND") (class "Default")
      (node (ref "C39") (pin "2") (pintype "passive"))
      (node (ref "C41") (pin "2") (pintype "passive"))
      (node (ref "C44") (pin "2") (pintype "passive"))
      (node (ref "C45") (pin "1") (pintype "passive"))
      (node (ref "C46") (pin "1") (pintype "passive"))
      (node (ref "C47") (pin "1") (pintype "passive"))
      (node (ref "D24") (pin "1") (pintype "passive"))
      (node (ref "D25") (pin "1") (pintype "passive"))
      (node (ref "D30") (pin "1") (pintype "passive"))
      (node (ref "D31") (pin "1") (pintype "passive"))
      (node (ref "J3") (pin "2") (pintype "passive"))
      (node (ref "L4") (pin "2") (pinfunction "2_2") (pintype "passive"))
      (node (ref "L5") (pin "2") (pinfunction "2_2") (pintype "passive"))
      (node (ref "LED1") (pin "2") (pintype "passive"))
      (node (ref "LED2") (pin "2") (pintype "passive"))
      (node (ref "LED3") (pin "2") (pintype "passive"))
      (node (ref "LED4") (pin "2") (pintype "passive"))
      (node (ref "Q3") (pin "3") (pintype "passive"))
      (node (ref "Q4") (pin "3") (pintype "passive"))
      (node (ref "Q7") (pin "3") (pintype "passive"))
      (node (ref "Q8") (pin "3") (pintype "passive"))
      (node (ref "R36") (pin "1") (pinfunction "1_1") (pintype "passive"))
      (node (ref "R36") (pin "2") (pinfunction "2_2") (pintype "passive"))
      (node (ref "R36") (pin "3") (pinfunction "3_3") (pintype "passive"))
      (node (ref "R36") (pin "4") (pinfunction "4_4") (pintype "passive"))
      (node (ref "R39") (pin "1") (pintype "passive"))
      (node (ref "R41") (pin "2") (pintype "passive"))
      (node (ref "U10") (pin "1") (pinfunction "GND_1") (pintype "passive"))
      (node (ref "U4") (pin "4") (pinfunction "COM_4") (pintype "passive"))
      (node (ref "U5") (pin "4") (pinfunction "COM_4") (pintype "passive"))
      (node (ref "U6") (pin "4") (pinfunction "COM_4") (pintype "passive"))
      (node (ref "U7") (pin "4") (pinfunction "COM_4") (pintype "passive"))
      (node (ref "U8") (pin "10") (pinfunction "GND_10") (pintype "passive"))
      (node (ref "U8") (pin "11") (pinfunction "B7_11") (pintype "passive"))
      (node (ref "U8") (pin "12") (pinfunction "B6_12") (pintype "passive"))
      (node (ref "U8") (pin "13") (pinfunction "B5_13") (pintype "passive"))
      (node (ref "U8") (pin "14") (pinfunction "B4_14") (pintype "passive"))
      (node (ref "U8") (pin "19") (pinfunction "~{OE}_19") (pintype "passive"))
      (node (ref "U8") (pin "6") (pinfunction "A4_6") (pintype "passive"))
      (node (ref "U8") (pin "7") (pinfunction "A5_7") (pintype "passive"))
      (node (ref "U8") (pin "8") (pinfunction "A6_8") (pintype "passive"))
      (node (ref "U8") (pin "9") (pinfunction "A7_9") (pintype "passive"))
      (node (ref "U9") (pin "2") (pinfunction "GND_2") (pintype "passive"))
    )
    (net (code "103") (name "SGND") (class "Default")
      (node (ref "C1") (pin "1") (pintype "passive"))
      (node (ref "C11") (pin "1") (pintype "passive"))
      (node (ref "C12") (pin "1") (pintype "passive"))
      (node (ref "C13") (pin "1") (pintype "passive"))
      (node (ref "C18") (pin "2") (pintype "passive"))
      (node (ref "C25") (pin "1") (pintype "passive"))
      (node (ref "C26") (pin "2") (pintype "passive"))
      (node (ref "C27") (pin "1") (pintype "passive"))
      (node (ref "C29") (pin "2") (pintype "passive"))
      (node (ref "C31") (pin "1") (pintype "passive"))
      (node (ref "C32") (pin "1") (pintype "passive"))
      (node (ref "C33") (pin "1") (pintype "passive"))
      (node (ref "C34") (pin "1") (pintype "passive"))
      (node (ref "C38") (pin "1") (pintype "passive"))
      (node (ref "C40") (pin "2") (pintype "passive"))
      (node (ref "C42") (pin "2") (pintype "passive"))
      (node (ref "C43") (pin "1") (pintype "passive"))
      (node (ref "D16") (pin "1") (pintype "passive"))
      (node (ref "D22") (pin "1") (pintype "passive"))
      (node (ref "H1") (pin "4") (pintype "passive"))
      (node (ref "H2") (pin "1") (pintype "passive"))
      (node (ref "H3") (pin "4") (pintype "passive"))
      (node (ref "H4") (pin "4") (pintype "passive"))
      (node (ref "H5") (pin "3") (pintype "passive"))
      (node (ref "H6") (pin "5") (pintype "passive"))
      (node (ref "KEY1") (pin "2") (pintype "passive"))
      (node (ref "KEY2") (pin "2") (pintype "passive"))
      (node (ref "KEY3") (pin "2") (pintype "passive"))
      (node (ref "KEY4") (pin "1") (pintype "passive"))
      (node (ref "KEY5") (pin "1") (pintype "passive"))
      (node (ref "KEY6") (pin "1") (pintype "passive"))
      (node (ref "L4") (pin "1") (pinfunction "1_1") (pintype "passive"))
      (node (ref "L5") (pin "1") (pinfunction "1_1") (pintype "passive"))
      (node (ref "M1") (pin "7") (pinfunction "GND_7") (pintype "passive"))
      (node (ref "MCU1") (pin "12") (pinfunction "VSS/VSSA_12") (pintype "passive"))
      (node (ref "MCU1") (pin "48") (pinfunction "VSS_48") (pintype "passive"))
      (node (ref "MCU1") (pin "69") (pinfunction "VSS_69") (pintype "passive"))
      (node (ref "OLED") (pin "1") (pinfunction "GND_1") (pintype "passive"))
      (node (ref "Q9") (pin "3") (pinfunction "3_3") (pintype "passive"))
      (node (ref "R1") (pin "1") (pintype "passive"))
      (node (ref "R19") (pin "2") (pintype "passive"))
      (node (ref "R20") (pin "2") (pintype "passive"))
      (node (ref "R21") (pin "2") (pintype "passive"))
      (node (ref "R8") (pin "1") (pintype "passive"))
      (node (ref "RST") (pin "2") (pintype "passive"))
      (node (ref "SW1") (pin "5") (pintype "passive"))
      (node (ref "SW1") (pin "6") (pintype "passive"))
      (node (ref "SW1") (pin "7") (pintype "passive"))
      (node (ref "SW1") (pin "8") (pintype "passive"))
      (node (ref "U2") (pin "1") (pinfunction "GND_1") (pintype "passive"))
      (node (ref "U3") (pin "1") (pinfunction "GND_1") (pintype "passive"))
      (node (ref "X1") (pin "2") (pinfunction "GND_2") (pintype "passive"))
    )
    (net (code "104") (name "VCC") (class "Default")
      (node (ref "C46") (pin "2") (pintype "passive"))
      (node (ref "C47") (pin "2") (pintype "passive"))
      (node (ref "D20") (pin "2") (pintype "passive"))
      (node (ref "D21") (pin "2") (pintype "passive"))
      (node (ref "D28") (pin "2") (pintype "passive"))
      (node (ref "D29") (pin "2") (pintype "passive"))
      (node (ref "D33") (pin "1") (pintype "passive"))
      (node (ref "D34") (pin "1") (pintype "passive"))
      (node (ref "Power") (pin "4") (pinfunction "4_4") (pintype "passive"))
      (node (ref "Q1") (pin "2") (pintype "passive"))
      (node (ref "Q2") (pin "2") (pintype "passive"))
      (node (ref "Q5") (pin "2") (pintype "passive"))
      (node (ref "Q6") (pin "2") (pintype "passive"))
    )
    (net (code "105") (name "VCC5V") (class "Default")
      (node (ref "C13") (pin "2") (pintype "passive"))
      (node (ref "C25") (pin "2") (pintype "passive"))
      (node (ref "C26") (pin "1") (pintype "passive"))
      (node (ref "C27") (pin "2") (pintype "passive"))
      (node (ref "C42") (pin "1") (pintype "passive"))
      (node (ref "D1") (pin "1") (pintype "passive"))
      (node (ref "D12") (pin "1") (pintype "passive"))
      (node (ref "D16") (pin "2") (pintype "passive"))
      (node (ref "D23") (pin "1") (pintype "passive"))
      (node (ref "H6") (pin "6") (pintype "passive"))
      (node (ref "L2") (pin "2") (pinfunction "2_2") (pintype "passive"))
      (node (ref "MCU1") (pin "49") (pinfunction "VDD_49") (pintype "passive"))
      (node (ref "MCU1") (pin "70") (pinfunction "VDD_70") (pintype "passive"))
      (node (ref "MCU1") (pin "8") (pinfunction "VDD_8") (pintype "passive"))
      (node (ref "R11") (pin "1") (pintype "passive"))
      (node (ref "R27") (pin "1") (pinfunction "1_1") (pintype "passive"))
      (node (ref "R27") (pin "2") (pinfunction "2_2") (pintype "passive"))
      (node (ref "R27") (pin "3") (pinfunction "3_3") (pintype "passive"))
      (node (ref "R27") (pin "4") (pinfunction "4_4") (pintype "passive"))
      (node (ref "R28") (pin "5") (pinfunction "5_5") (pintype "passive"))
      (node (ref "R28") (pin "6") (pinfunction "6_6") (pintype "passive"))
      (node (ref "R28") (pin "7") (pinfunction "7_7") (pintype "passive"))
      (node (ref "R28") (pin "8") (pinfunction "8_8") (pintype "passive"))
      (node (ref "R31") (pin "7") (pinfunction "7_7") (pintype "passive"))
      (node (ref "R31") (pin "8") (pinfunction "8_8") (pintype "passive"))
      (node (ref "R35") (pin "5") (pinfunction "5_5") (pintype "passive"))
      (node (ref "R35") (pin "6") (pinfunction "6_6") (pintype "passive"))
      (node (ref "R35") (pin "7") (pinfunction "7_7") (pintype "passive"))
      (node (ref "R35") (pin "8") (pinfunction "8_8") (pintype "passive"))
      (node (ref "U2") (pin "0") (pinfunction "OUT_0") (pintype "passive"))
      (node (ref "U2") (pin "2") (pinfunction "OUT_2") (pintype "passive"))
    )
    (net (code "106") (name "VCC5V-2") (class "Default")
      (node (ref "B1") (pin "1") (pintype "passive"))
      (node (ref "C29") (pin "1") (pintype "passive"))
      (node (ref "C31") (pin "2") (pintype "passive"))
      (node (ref "C33") (pin "2") (pintype "passive"))
      (node (ref "C34") (pin "2") (pintype "passive"))
      (node (ref "C38") (pin "2") (pintype "passive"))
      (node (ref "C40") (pin "1") (pintype "passive"))
      (node (ref "D22") (pin "2") (pintype "passive"))
      (node (ref "H3") (pin "2") (pintype "passive"))
      (node (ref "H4") (pin "2") (pintype "passive"))
      (node (ref "H5") (pin "4") (pintype "passive"))
      (node (ref "M1") (pin "1") (pinfunction "CLR1_1") (pintype "passive"))
      (node (ref "M1") (pin "10") (pinfunction "PR2_10") (pintype "passive"))
      (node (ref "M1") (pin "13") (pinfunction "CLR2_13") (pintype "passive"))
      (node (ref "M1") (pin "14") (pinfunction "VCC_14") (pintype "passive"))
      (node (ref "M1") (pin "4") (pinfunction "PR1_4") (pintype "passive"))
      (node (ref "OLED") (pin "2") (pinfunction "VCC_2") (pintype "passive"))
      (node (ref "R26") (pin "5") (pinfunction "5_5") (pintype "passive"))
      (node (ref "R26") (pin "6") (pinfunction "6_6") (pintype "passive"))
      (node (ref "R26") (pin "7") (pinfunction "7_7") (pintype "passive"))
      (node (ref "R26") (pin "8") (pinfunction "8_8") (pintype "passive"))
      (node (ref "U3") (pin "0") (pinfunction "OUT_0") (pintype "passive"))
      (node (ref "U3") (pin "2") (pinfunction "OUT_2") (pintype "passive"))
    )
    (net (code "107") (name "VCC7.2V") (class "Default")
      (node (ref "C43") (pin "2") (pintype "passive"))
      (node (ref "D14") (pin "1") (pintype "passive"))
      (node (ref "D19") (pin "1") (pintype "passive"))
      (node (ref "D2") (pin "1") (pintype "passive"))
      (node (ref "Power") (pin "3") (pinfunction "3_3") (pintype "passive"))
    )
    (net (code "108") (name "VCC15V") (class "Default")
      (node (ref "C41") (pin "1") (pintype "passive"))
      (node (ref "D17") (pin "1") (pintype "passive"))
      (node (ref "D18") (pin "1") (pintype "passive"))
      (node (ref "D26") (pin "1") (pintype "passive"))
      (node (ref "D27") (pin "1") (pintype "passive"))
      (node (ref "D32") (pin "2") (pintype "passive"))
      (node (ref "R34") (pin "2") (pintype "passive"))
      (node (ref "U4") (pin "1") (pinfunction "VCC_1") (pintype "passive"))
      (node (ref "U4") (pin "3") (pinfunction "~{SD}_3") (pintype "passive"))
      (node (ref "U5") (pin "1") (pinfunction "VCC_1") (pintype "passive"))
      (node (ref "U5") (pin "3") (pinfunction "~{SD}_3") (pintype "passive"))
      (node (ref "U6") (pin "1") (pinfunction "VCC_1") (pintype "passive"))
      (node (ref "U6") (pin "3") (pinfunction "~{SD}_3") (pintype "passive"))
      (node (ref "U7") (pin "1") (pinfunction "VCC_1") (pintype "passive"))
      (node (ref "U7") (pin "3") (pinfunction "~{SD}_3") (pintype "passive"))
    )
    (net (code "109") (name "unconnected-(M1-~{Q}1-Pad6)") (class "Default")
      (node (ref "M1") (pin "6") (pinfunction "~{Q}1_6") (pintype "passive"))
    )
    (net (code "110") (name "unconnected-(M1-~{Q}2-Pad8)") (class "Default")
      (node (ref "M1") (pin "8") (pinfunction "~{Q}2_8") (pintype "passive"))
    )
    (net (code "111") (name "unconnected-(MCU1-PTA0{slash}FTM0_CH0-Pad62)") (class "Default")
      (node (ref "MCU1") (pin "62") (pinfunction "PTA0/FTM0_CH0_62") (pintype "passive"))
    )
    (net (code "112") (name "unconnected-(MCU1-PTA1{slash}FTM0_CH1-Pad61)") (class "Default")
      (node (ref "MCU1") (pin "61") (pinfunction "PTA1/FTM0_CH1_61") (pintype "passive"))
    )
    (net (code "113") (name "unconnected-(MCU1-PTA6{slash}ADC0_SE2{slash}FTM2_ALT1-Pad46)") (class "Default")
      (node (ref "MCU1") (pin "46") (pinfunction "PTA6/ADC0_SE2/FTM2_ALT1_46") (pintype "passive"))
    )
    (net (code "114") (name "unconnected-(MCU1-PTA7{slash}ADC0_SE3{slash}FTM2_FLT2-Pad45)") (class "Default")
      (node (ref "MCU1") (pin "45") (pinfunction "PTA7/ADC0_SE3/FTM2_FLT2_45") (pintype "passive"))
    )
    (net (code "115") (name "unconnected-(MCU1-PTB0{slash}UART0_RX{slash}ADC0_SE4-Pad42)") (class "Default")
      (node (ref "MCU1") (pin "42") (pinfunction "PTB0/UART0_RX/ADC0_SE4_42") (pintype "passive"))
    )
    (net (code "116") (name "unconnected-(MCU1-PTB1{slash}UART0_TX{slash}ADC0_SE5-Pad41)") (class "Default")
      (node (ref "MCU1") (pin "41") (pinfunction "PTB1/UART0_TX/ADC0_SE5_41") (pintype "passive"))
    )
    (net (code "117") (name "unconnected-(MCU1-PTB2{slash}FTM0_CH0{slash}ADC0_SE6-Pad40)") (class "Default")
      (node (ref "MCU1") (pin "40") (pinfunction "PTB2/FTM0_CH0/ADC0_SE6_40") (pintype "passive"))
    )
    (net (code "118") (name "unconnected-(MCU1-PTB3{slash}FTM0_CH1{slash}ADC0_SE7-Pad39)") (class "Default")
      (node (ref "MCU1") (pin "39") (pinfunction "PTB3/FTM0_CH1/ADC0_SE7_39") (pintype "passive"))
    )
    (net (code "119") (name "unconnected-(MCU1-PTC0{slash}FTM2_CH0-Pad32)") (class "Default")
      (node (ref "MCU1") (pin "32") (pinfunction "PTC0/FTM2_CH0_32") (pintype "passive"))
    )
    (net (code "120") (name "unconnected-(MCU1-PTC1{slash}FTM2_CH1-Pad31)") (class "Default")
      (node (ref "MCU1") (pin "31") (pinfunction "PTC1/FTM2_CH1_31") (pintype "passive"))
    )
    (net (code "121") (name "unconnected-(MCU1-PTC5-Pad77)") (class "Default")
      (node (ref "MCU1") (pin "77") (pinfunction "PTC5_77") (pintype "passive"))
    )
    (net (code "122") (name "unconnected-(MCU1-PTC6{slash}UART1_RX-Pad64)") (class "Default")
      (node (ref "MCU1") (pin "64") (pinfunction "PTC6/UART1_RX_64") (pintype "passive"))
    )
    (net (code "123") (name "unconnected-(MCU1-PTC7{slash}UART1_TX-Pad63)") (class "Default")
      (node (ref "MCU1") (pin "63") (pinfunction "PTC7/UART1_TX_63") (pintype "passive"))
    )
    (net (code "124") (name "unconnected-(MCU1-PTD0{slash}FTM2_CH2-Pad2)") (class "Default")
      (node (ref "MCU1") (pin "2") (pinfunction "PTD0/FTM2_CH2_2") (pintype "passive"))
    )
    (net (code "125") (name "unconnected-(MCU1-PTD1{slash}FTM_CH3-Pad1)") (class "Default")
      (node (ref "MCU1") (pin "1") (pinfunction "PTD1/FTM_CH3_1") (pintype "passive"))
    )
    (net (code "126") (name "unconnected-(MCU1-PTE2-Pad68)") (class "Default")
      (node (ref "MCU1") (pin "68") (pinfunction "PTE2_68") (pintype "passive"))
    )
    (net (code "127") (name "unconnected-(MCU1-PTE3-Pad67)") (class "Default")
      (node (ref "MCU1") (pin "67") (pinfunction "PTE3_67") (pintype "passive"))
    )
    (net (code "128") (name "unconnected-(MCU1-PTE4-Pad47)") (class "Default")
      (node (ref "MCU1") (pin "47") (pinfunction "PTE4_47") (pintype "passive"))
    )
    (net (code "129") (name "unconnected-(MCU1-PTF2{slash}UART1_RX-Pad44)") (class "Default")
      (node (ref "MCU1") (pin "44") (pinfunction "PTF2/UART1_RX_44") (pintype "passive"))
    )
    (net (code "130") (name "unconnected-(MCU1-PTF3{slash}UART1_TX-Pad43)") (class "Default")
      (node (ref "MCU1") (pin "43") (pinfunction "PTF3/UART1_TX_43") (pintype "passive"))
    )
    (net (code "131") (name "unconnected-(MCU1-PTG6{slash}FTM2_CH4-Pad51)") (class "Default")
      (node (ref "MCU1") (pin "51") (pinfunction "PTG6/FTM2_CH4_51") (pintype "passive"))
    )
    (net (code "132") (name "unconnected-(MCU1-PTG7{slash}FTM2_CH5-Pad50)") (class "Default")
      (node (ref "MCU1") (pin "50") (pinfunction "PTG7/FTM2_CH5_50") (pintype "passive"))
    )
    (net (code "133") (name "unconnected-(MCU1-PTH2{slash}FTM1_CH0-Pad7)") (class "Default")
      (node (ref "MCU1") (pin "7") (pinfunction "PTH2/FTM1_CH0_7") (pintype "passive"))
    )
    (net (code "134") (name "unconnected-(MCU1-PTH5-Pad5)") (class "Default")
      (node (ref "MCU1") (pin "5") (pinfunction "PTH5_5") (pintype "passive"))
    )
    (net (code "135") (name "unconnected-(MCU1-PTI1{slash}IRQ{slash}UART2_TX-Pad16)") (class "Default")
      (node (ref "MCU1") (pin "16") (pinfunction "PTI1/IRQ/UART2_TX_16") (pintype "passive"))
    )
    (net (code "136") (name "unconnected-(MCU1-PTI2{slash}IRQ-Pad66)") (class "Default")
      (node (ref "MCU1") (pin "66") (pinfunction "PTI2/IRQ_66") (pintype "passive"))
    )
    (net (code "137") (name "unconnected-(MCU1-PTI3{slash}IRQ-Pad65)") (class "Default")
      (node (ref "MCU1") (pin "65") (pinfunction "PTI3/IRQ_65") (pintype "passive"))
    )
    (net (code "138") (name "unconnected-(MCU1-PTI4{slash}IRQ-Pad15)") (class "Default")
      (node (ref "MCU1") (pin "15") (pinfunction "PTI4/IRQ_15") (pintype "passive"))
    )
    (net (code "139") (name "unconnected-(Power-Pad1)") (class "Default")
      (node (ref "Power") (pin "1") (pinfunction "1_1") (pintype "passive"))
    )
    (net (code "140") (name "unconnected-(Power-Pad6)") (class "Default")
      (node (ref "Power") (pin "6") (pinfunction "6_6") (pintype "passive"))
    )
    (net (code "141") (name "unconnected-(U9-NC-Pad6)") (class "Default")
      (node (ref "U9") (pin "6") (pinfunction "NC_6") (pintype "passive+no_connect"))
    )
  )
)
